# furball-mini.net
KiCad netlist of a schematic drawn in EAGLE
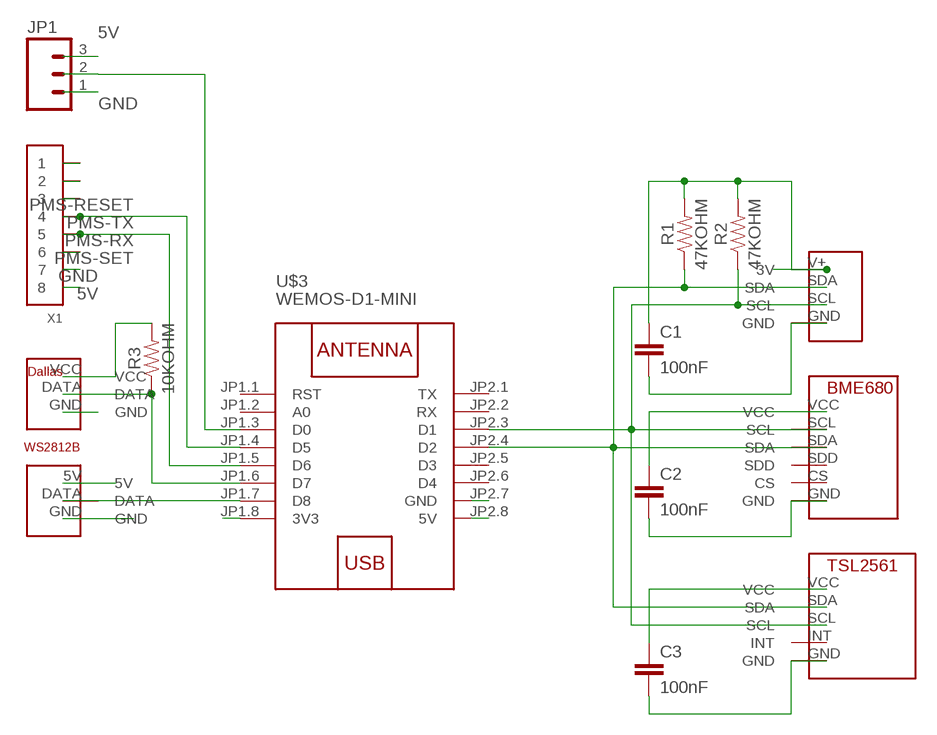
[diagram p0: schematic, sheet 1]

(export (version "E")
  (design (tool "Eeschema 10.0.6"))
  (components
    (comp (ref "C1")
      (value "100nF")
      (footprint "eagle-import:CAP-PTH-LARGE")
      (libsource (lib "eagle-import") (part "CAPPTH3"))
    )
    (comp (ref "C2")
      (value "100nF")
      (footprint "eagle-import:CAP-PTH-LARGE")
      (libsource (lib "eagle-import") (part "CAPPTH3"))
    )
    (comp (ref "C3")
      (value "100nF")
      (footprint "eagle-import:CAP-PTH-LARGE")
      (libsource (lib "eagle-import") (part "CAPPTH3"))
    )
    (comp (ref "JP1")
      (value "M03PTH")
      (footprint "eagle-import:1X03")
      (libsource (lib "eagle-import") (part "M03PTH"))
    )
    (comp (ref "R1")
      (value "47KOHM")
      (footprint "eagle-import:AXIAL-0.3-KIT")
      (libsource (lib "eagle-import") (part "47KOHM"))
    )
    (comp (ref "R2")
      (value "47KOHM")
      (footprint "eagle-import:AXIAL-0.3-KIT")
      (libsource (lib "eagle-import") (part "47KOHM"))
    )
    (comp (ref "R3")
      (value "10KOHM")
      (footprint "eagle-import:AXIAL-0.3-KIT")
      (libsource (lib "eagle-import") (part "47KOHM"))
    )
    (comp (ref "U$1")
      (value "WS2812BHEADER")
      (footprint "eagle-import:WS2812BHEADER")
      (libsource (lib "eagle-import") (part "WS2812BHEADER"))
    )
    (comp (ref "U$2")
      (value "I2CHEADER")
      (footprint "eagle-import:I2CHEADER")
      (libsource (lib "eagle-import") (part "I2CHEADER"))
    )
    (comp (ref "U$3")
      (value "WEMOS-D1-MINI")
      (footprint "eagle-import:WEMOS-D1-MINI")
      (libsource (lib "eagle-import") (part "WEMOS-D1-MINI"))
    )
    (comp (ref "U$4")
      (value "BME680BREAKOUT")
      (footprint "eagle-import:BME680BREAKOUT")
      (libsource (lib "eagle-import") (part "BME680BREAKOUT"))
    )
    (comp (ref "U$5")
      (value "DALLASONEWIREHEADER")
      (footprint "eagle-import:DALLASONEWIREHEADER")
      (libsource (lib "eagle-import") (part "DALLASONEWIREHEADER"))
    )
    (comp (ref "U$6")
      (value "TSL2561BREAKOUT")
      (footprint "eagle-import:TSL2561BREAKOUT")
      (libsource (lib "eagle-import") (part "TSL2561BREAKOUT"))
    )
    (comp (ref "X1")
      (value "CONN_8-1-53261")
      (footprint "eagle-import:PB-53261-08")
      (libsource (lib "eagle-import") (part "CONN_8-1-53261"))
    )
  )
  (nets
    (net (code "1") (name "/3V3") (class "Default")
      (node (ref "C1") (pin "1") (pinfunction "1_1") (pintype "passive"))
      (node (ref "C2") (pin "1") (pinfunction "1_1") (pintype "passive"))
      (node (ref "C3") (pin "1") (pinfunction "1_1") (pintype "passive"))
      (node (ref "R1") (pin "P$2") (pinfunction "2_P$2") (pintype "passive"))
      (node (ref "R2") (pin "P$2") (pinfunction "2_P$2") (pintype "passive"))
      (node (ref "R3") (pin "P$2") (pinfunction "2_P$2") (pintype "passive"))
      (node (ref "U$2") (pin "V+") (pinfunction "3V_V+") (pintype "power_in"))
      (node (ref "U$3") (pin "JP1.8") (pinfunction "3V3_JP1.8") (pintype "power_in"))
      (node (ref "U$4") (pin "VCC") (pinfunction "VCC_VCC") (pintype "power_in"))
      (node (ref "U$5") (pin "VCC") (pinfunction "VCC_VCC") (pintype "power_in"))
      (node (ref "U$6") (pin "VCC") (pinfunction "VCC_VCC") (pintype "power_in"))
    )
    (net (code "2") (name "/5V") (class "Default")
      (node (ref "JP1") (pin "3") (pinfunction "3_3") (pintype "passive"))
      (node (ref "U$1") (pin "5V") (pinfunction "5V_5V") (pintype "power_in"))
      (node (ref "U$3") (pin "JP2.8") (pinfunction "5V_JP2.8") (pintype "power_in"))
      (node (ref "X1") (pin "8") (pinfunction "8_8") (pintype "bidirectional"))
    )
    (net (code "3") (name "/GND") (class "Default")
      (node (ref "C1") (pin "2") (pinfunction "2_2") (pintype "passive"))
      (node (ref "C2") (pin "2") (pinfunction "2_2") (pintype "passive"))
      (node (ref "C3") (pin "2") (pinfunction "2_2") (pintype "passive"))
      (node (ref "JP1") (pin "1") (pinfunction "1_1") (pintype "passive"))
      (node (ref "U$1") (pin "GND") (pinfunction "GND_GND") (pintype "power_in"))
      (node (ref "U$2") (pin "GND") (pinfunction "GND_GND") (pintype "power_in"))
      (node (ref "U$3") (pin "JP2.7") (pinfunction "GND_JP2.7") (pintype "power_in"))
      (node (ref "U$4") (pin "GND") (pinfunction "GND_GND") (pintype "power_in"))
      (node (ref "U$5") (pin "GND") (pinfunction "GND_GND") (pintype "power_in"))
      (node (ref "U$6") (pin "GND") (pinfunction "GND_GND") (pintype "power_in"))
      (node (ref "X1") (pin "7") (pinfunction "7_7") (pintype "bidirectional"))
    )
    (net (code "4") (name "/PMS-RESET") (class "Default")
      (node (ref "X1") (pin "3") (pinfunction "3_3") (pintype "bidirectional"))
    )
    (net (code "5") (name "/PMS-RX") (class "Default")
      (node (ref "U$3") (pin "JP1.5") (pinfunction "D6_JP1.5") (pintype "bidirectional"))
      (node (ref "X1") (pin "5") (pinfunction "5_5") (pintype "bidirectional"))
    )
    (net (code "6") (name "/PMS-SET") (class "Default")
      (node (ref "X1") (pin "6") (pinfunction "6_6") (pintype "bidirectional"))
    )
    (net (code "7") (name "/PMS-TX") (class "Default")
      (node (ref "U$3") (pin "JP1.4") (pinfunction "D5_JP1.4") (pintype "bidirectional"))
      (node (ref "X1") (pin "4") (pinfunction "4_4") (pintype "bidirectional"))
    )
    (net (code "8") (name "Net-(R1-1)") (class "Default")
      (node (ref "R1") (pin "P$1") (pinfunction "1_P$1") (pintype "passive"))
      (node (ref "U$2") (pin "SDA") (pinfunction "SDA_SDA") (pintype "bidirectional"))
      (node (ref "U$3") (pin "JP2.4") (pinfunction "D2_JP2.4") (pintype "bidirectional"))
      (node (ref "U$4") (pin "SDA") (pinfunction "SDA_SDA") (pintype "bidirectional"))
      (node (ref "U$6") (pin "SDA") (pinfunction "SDA_SDA") (pintype "bidirectional"))
    )
    (net (code "9") (name "Net-(R2-1)") (class "Default")
      (node (ref "R2") (pin "P$1") (pinfunction "1_P$1") (pintype "passive"))
      (node (ref "U$2") (pin "SCL") (pinfunction "SCL_SCL") (pintype "bidirectional"))
      (node (ref "U$3") (pin "JP2.3") (pinfunction "D1_JP2.3") (pintype "bidirectional"))
      (node (ref "U$4") (pin "SCL") (pinfunction "SCL_SCL") (pintype "bidirectional"))
      (node (ref "U$6") (pin "SCL") (pinfunction "SCL_SCL") (pintype "bidirectional"))
    )
    (net (code "10") (name "Net-(R3-1)") (class "Default")
      (node (ref "R3") (pin "P$1") (pinfunction "1_P$1") (pintype "passive"))
      (node (ref "U$3") (pin "JP1.6") (pinfunction "D7_JP1.6") (pintype "bidirectional"))
      (node (ref "U$5") (pin "DATA") (pinfunction "DATA_DATA") (pintype "bidirectional"))
    )
    (net (code "11") (name "Net-(U$3-D0)") (class "Default")
      (node (ref "JP1") (pin "2") (pinfunction "2_2") (pintype "passive"))
      (node (ref "U$3") (pin "JP1.3") (pinfunction "D0_JP1.3") (pintype "bidirectional"))
    )
    (net (code "12") (name "Net-(U$3-D8)") (class "Default")
      (node (ref "U$1") (pin "DATA") (pinfunction "DATA_DATA") (pintype "bidirectional"))
      (node (ref "U$3") (pin "JP1.7") (pinfunction "D8_JP1.7") (pintype "bidirectional"))
    )
    (net (code "13") (name "unconnected-(U$3-A0-PadJP1.2)") (class "Default")
      (node (ref "U$3") (pin "JP1.2") (pinfunction "A0_JP1.2") (pintype "bidirectional"))
    )
    (net (code "14") (name "unconnected-(U$3-D3-PadJP2.5)") (class "Default")
      (node (ref "U$3") (pin "JP2.5") (pinfunction "D3_JP2.5") (pintype "bidirectional"))
    )
    (net (code "15") (name "unconnected-(U$3-D4-PadJP2.6)") (class "Default")
      (node (ref "U$3") (pin "JP2.6") (pinfunction "D4_JP2.6") (pintype "bidirectional"))
    )
    (net (code "16") (name "unconnected-(U$3-RST-PadJP1.1)") (class "Default")
      (node (ref "U$3") (pin "JP1.1") (pinfunction "RST_JP1.1") (pintype "bidirectional"))
    )
    (net (code "17") (name "unconnected-(U$3-RX-PadJP2.2)") (class "Default")
      (node (ref "U$3") (pin "JP2.2") (pinfunction "RX_JP2.2") (pintype "bidirectional"))
    )
    (net (code "18") (name "unconnected-(U$3-TX-PadJP2.1)") (class "Default")
      (node (ref "U$3") (pin "JP2.1") (pinfunction "TX_JP2.1") (pintype "bidirectional"))
    )
    (net (code "19") (name "unconnected-(U$4-PadCS)") (class "Default")
      (node (ref "U$4") (pin "CS") (pinfunction "CS_CS") (pintype "bidirectional"))
    )
    (net (code "20") (name "unconnected-(U$4-PadSDD)") (class "Default")
      (node (ref "U$4") (pin "SDD") (pinfunction "SDD_SDD") (pintype "bidirectional"))
    )
    (net (code "21") (name "unconnected-(U$6-PadINT)") (class "Default")
      (node (ref "U$6") (pin "INT") (pinfunction "INT_INT") (pintype "output"))
    )
    (net (code "22") (name "unconnected-(X1-Pad1)") (class "Default")
      (node (ref "X1") (pin "1") (pinfunction "1_1") (pintype "bidirectional"))
    )
    (net (code "23") (name "unconnected-(X1-Pad2)") (class "Default")
      (node (ref "X1") (pin "2") (pinfunction "2_2") (pintype "bidirectional"))
    )
  )
)
